# QCopterFC_SD_Sch.net
KiCad netlist of a schematic drawn in Altium Designer
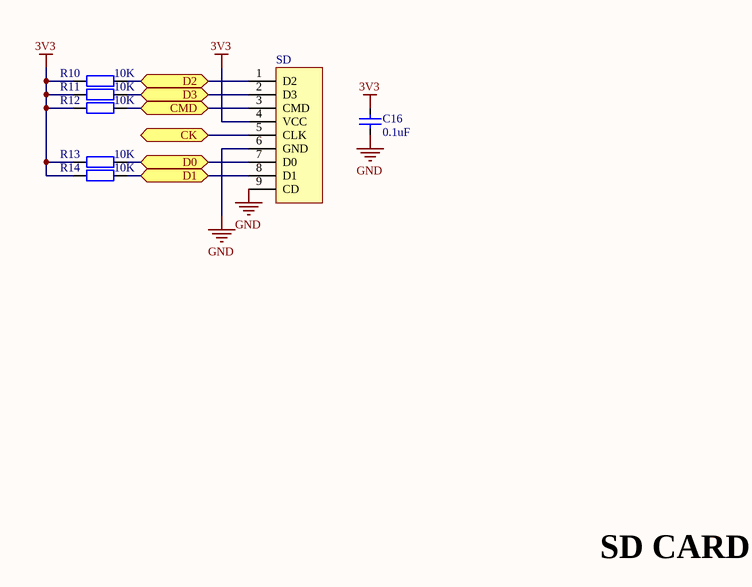
[diagram p0: QCopterFC_SD_Sch.SchDoc]

(export (version "E")
  (design (tool "Eeschema 10.0.6"))
  (components
    (comp (ref "C16")
      (value "0.1uF")
      (footprint "PCB_Passive:CAP_0603")
      (description "Capacitor")
      (fields (field (name "Comment") "Cap_0603"))
      (libsource (lib "SCH_Passive") (part "Cap_0603"))
    )
    (comp (ref "R10")
      (value "10K")
      (footprint "PCB_Passive:RES_0603")
      (description "Resistor")
      (fields (field (name "Comment") "Res_0603"))
      (libsource (lib "SCH_Passive") (part "Res_0603"))
    )
    (comp (ref "R11")
      (value "10K")
      (footprint "PCB_Passive:RES_0603")
      (description "Resistor")
      (fields (field (name "Comment") "Res_0603"))
      (libsource (lib "SCH_Passive") (part "Res_0603"))
    )
    (comp (ref "R12")
      (value "10K")
      (footprint "PCB_Passive:RES_0603")
      (description "Resistor")
      (fields (field (name "Comment") "Res_0603"))
      (libsource (lib "SCH_Passive") (part "Res_0603"))
    )
    (comp (ref "R13")
      (value "10K")
      (footprint "PCB_Passive:RES_0603")
      (description "Resistor")
      (fields (field (name "Comment") "Res_0603"))
      (libsource (lib "SCH_Passive") (part "Res_0603"))
    )
    (comp (ref "R14")
      (value "10K")
      (footprint "PCB_Passive:RES_0603")
      (description "Resistor")
      (fields (field (name "Comment") "Res_0603"))
      (libsource (lib "SCH_Passive") (part "Res_0603"))
    )
    (comp (ref "SD")
      (value "SD_Card_TF")
      (footprint "PCB_SDCard:SD_Card_TF")
      (description "SD")
      (libsource (lib "SCH_SDCard") (part "SD_Card_TF"))
    )
  )
  (nets
    (net (code "1") (name "/CK") (class "Default")
      (node (ref "SD") (pin "5") (pinfunction "CLK_5") (pintype "passive"))
    )
    (net (code "2") (name "/CMD") (class "Default")
      (node (ref "R12") (pin "2") (pinfunction "2_2") (pintype "passive"))
      (node (ref "SD") (pin "3") (pinfunction "CMD_3") (pintype "passive"))
    )
    (net (code "3") (name "/D0") (class "Default")
      (node (ref "R13") (pin "2") (pinfunction "2_2") (pintype "passive"))
      (node (ref "SD") (pin "7") (pinfunction "D0_7") (pintype "passive"))
    )
    (net (code "4") (name "/D1") (class "Default")
      (node (ref "R14") (pin "2") (pinfunction "2_2") (pintype "passive"))
      (node (ref "SD") (pin "8") (pinfunction "D1_8") (pintype "passive"))
    )
    (net (code "5") (name "/D2") (class "Default")
      (node (ref "R10") (pin "2") (pinfunction "2_2") (pintype "passive"))
      (node (ref "SD") (pin "1") (pinfunction "D2_1") (pintype "passive"))
    )
    (net (code "6") (name "/D3") (class "Default")
      (node (ref "R11") (pin "2") (pinfunction "2_2") (pintype "passive"))
      (node (ref "SD") (pin "2") (pinfunction "D3_2") (pintype "passive"))
    )
    (net (code "8") (name "3V3") (class "Default")
      (node (ref "C16") (pin "2") (pinfunction "2_2") (pintype "passive"))
      (node (ref "R10") (pin "1") (pinfunction "1_1") (pintype "passive"))
      (node (ref "R11") (pin "1") (pinfunction "1_1") (pintype "passive"))
      (node (ref "R12") (pin "1") (pinfunction "1_1") (pintype "passive"))
      (node (ref "R13") (pin "1") (pinfunction "1_1") (pintype "passive"))
      (node (ref "R14") (pin "1") (pinfunction "1_1") (pintype "passive"))
      (node (ref "SD") (pin "4") (pinfunction "VCC_4") (pintype "passive"))
    )
    (net (code "9") (name "GND") (class "Default")
      (node (ref "C16") (pin "1") (pinfunction "1_1") (pintype "passive"))
      (node (ref "SD") (pin "6") (pinfunction "GND_6") (pintype "passive"))
      (node (ref "SD") (pin "9") (pinfunction "CD_9") (pintype "passive"))
    )
  )
)
